# brobot19.net
KiCad netlist of a schematic drawn in EAGLE
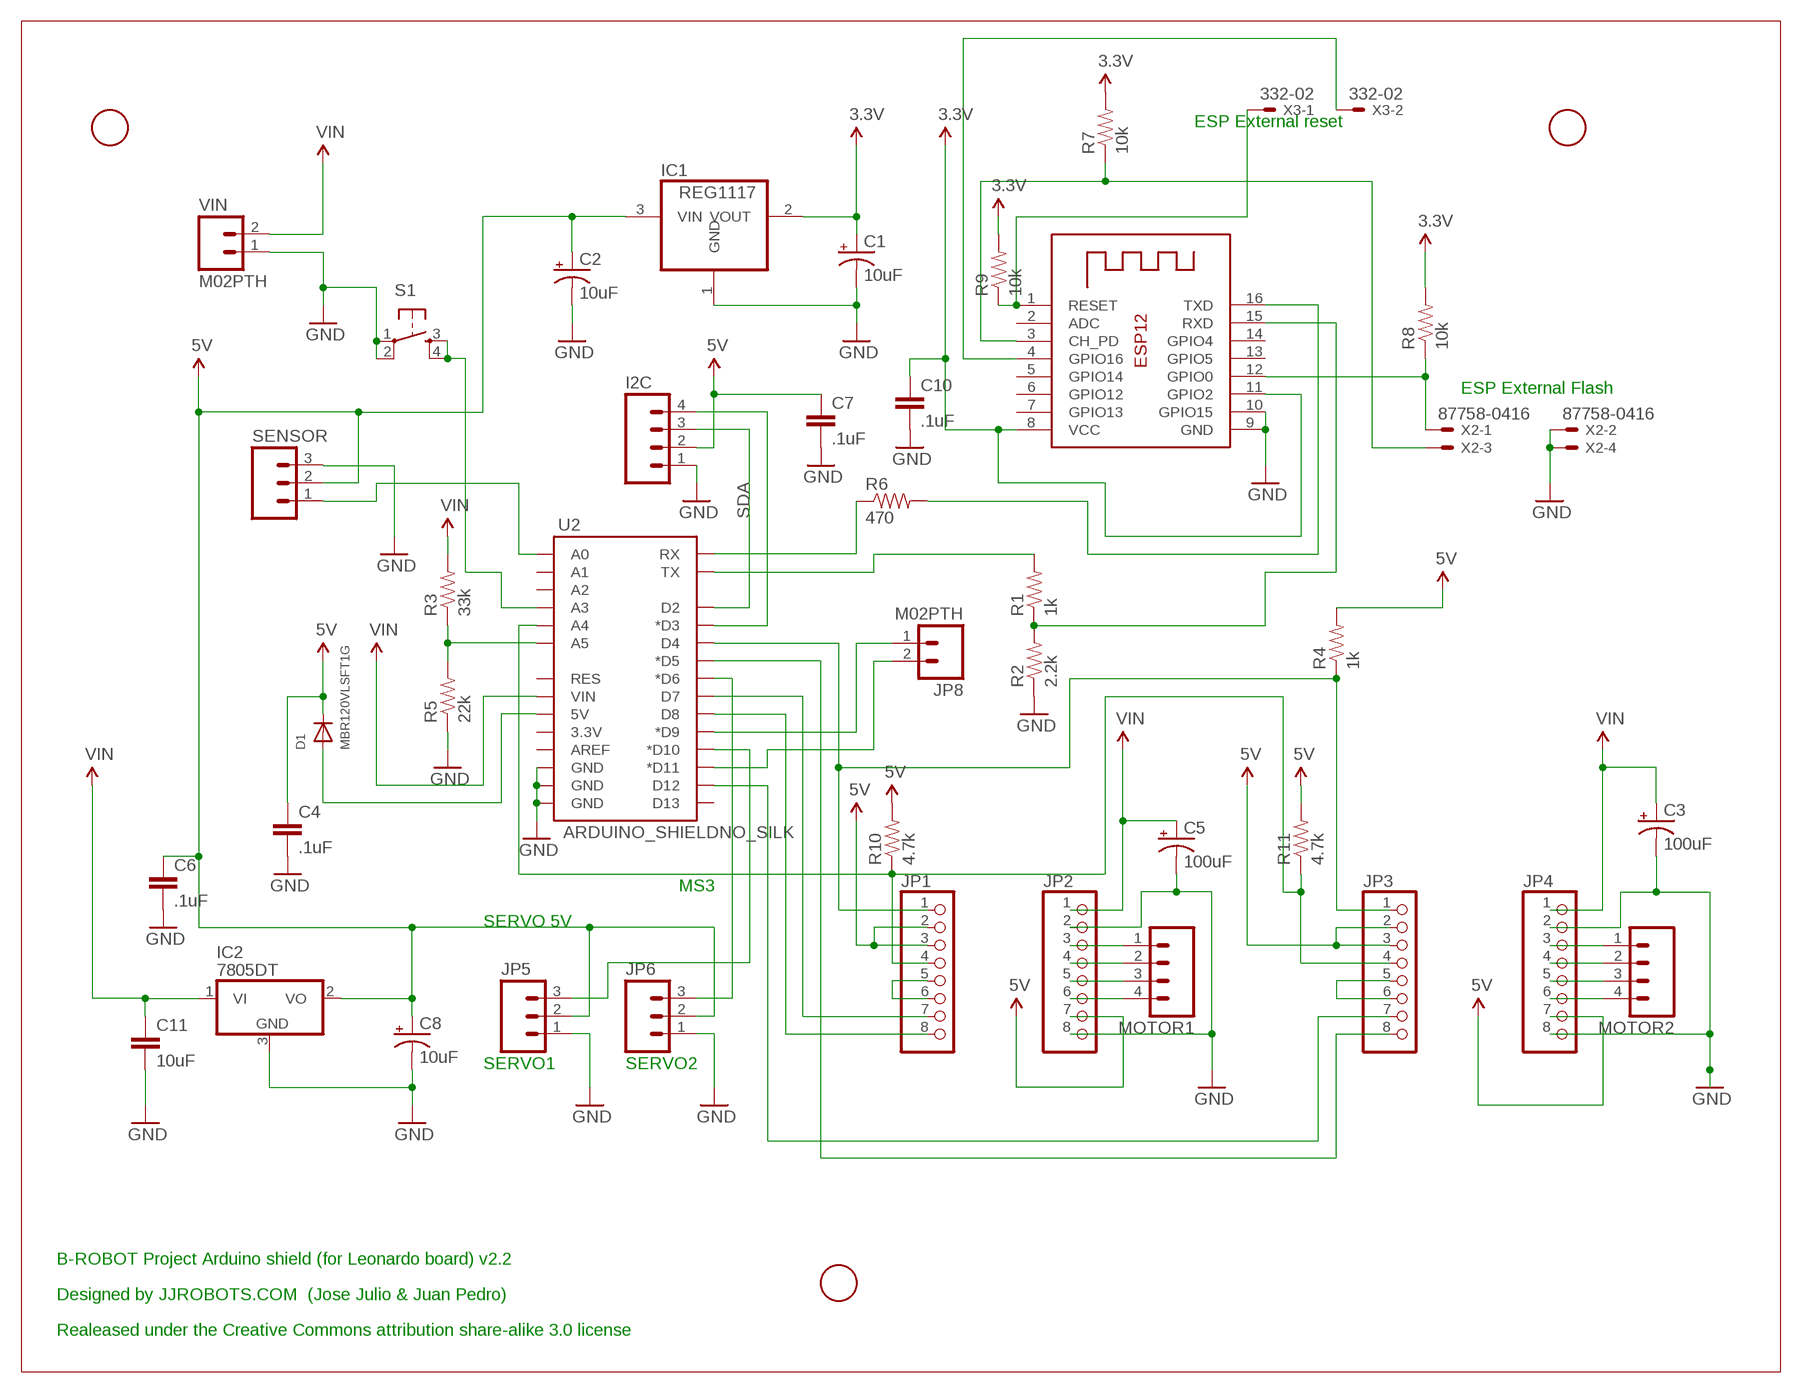
[diagram p0: schematic, sheet 1]

(export (version "E")
  (design (tool "Eeschema 10.0.6"))
  (components
    (comp (ref "C1")
      (value "10uF")
      (footprint "eagle-import:EIA3216")
      (libsource (lib "eagle-import") (part "CAP_POL1206"))
    )
    (comp (ref "C2")
      (value "10uF")
      (footprint "eagle-import:EIA3216")
      (libsource (lib "eagle-import") (part "CAP_POL1206"))
    )
    (comp (ref "C3")
      (value "100uF")
      (footprint "eagle-import:PANASONIC_D")
      (libsource (lib "eagle-import") (part "CAP_POLD"))
    )
    (comp (ref "C4")
      (value ".1uF")
      (footprint "eagle-import:0402-CAP")
      (libsource (lib "eagle-import") (part "CAP0402-CAP"))
    )
    (comp (ref "C5")
      (value "100uF")
      (footprint "eagle-import:PANASONIC_D")
      (libsource (lib "eagle-import") (part "CAP_POLD"))
    )
    (comp (ref "C6")
      (value ".1uF")
      (footprint "eagle-import:0402-CAP")
      (libsource (lib "eagle-import") (part "CAP0402-CAP"))
    )
    (comp (ref "C7")
      (value ".1uF")
      (footprint "eagle-import:0402-CAP")
      (libsource (lib "eagle-import") (part "CAP0402-CAP"))
    )
    (comp (ref "C8")
      (value "10uF")
      (footprint "eagle-import:EIA3216")
      (libsource (lib "eagle-import") (part "CAP_POL1206"))
    )
    (comp (ref "C10")
      (value ".1uF")
      (footprint "eagle-import:0402-CAP")
      (libsource (lib "eagle-import") (part "CAP0402-CAP"))
    )
    (comp (ref "C11")
      (value "10uF")
      (footprint "eagle-import:1206")
      (libsource (lib "eagle-import") (part "CAP1206"))
    )
    (comp (ref "D1")
      (value "MBR120VLSFT1G")
      (footprint "eagle-import:SOD-123")
      (libsource (lib "eagle-import") (part "DIODESOD-123"))
    )
    (comp (ref "I2C")
      (value "M04PTH")
      (footprint "eagle-import:1X04")
      (libsource (lib "eagle-import") (part "M04PTH"))
    )
    (comp (ref "IC1")
      (value "REG1117")
      (footprint "eagle-import:SOT223")
      (fields (field (name "MF") "LM1117MPX-3.3/NOPB"))
      (libsource (lib "eagle-import") (part "REG1117"))
    )
    (comp (ref "IC2")
      (value "7805DT")
      (footprint "eagle-import:TO252")
      (libsource (lib "eagle-import") (part "78DT05"))
    )
    (comp (ref "JP1")
      (value "PINHD-1X8")
      (footprint "eagle-import:1X08")
      (libsource (lib "eagle-import") (part "PINHD-1X8"))
    )
    (comp (ref "JP2")
      (value "PINHD-1X8")
      (footprint "eagle-import:1X08")
      (libsource (lib "eagle-import") (part "PINHD-1X8"))
    )
    (comp (ref "JP3")
      (value "PINHD-1X8")
      (footprint "eagle-import:1X08")
      (libsource (lib "eagle-import") (part "PINHD-1X8"))
    )
    (comp (ref "JP4")
      (value "PINHD-1X8")
      (footprint "eagle-import:1X08")
      (libsource (lib "eagle-import") (part "PINHD-1X8"))
    )
    (comp (ref "JP5")
      (value "M03PTH")
      (footprint "eagle-import:1X03")
      (libsource (lib "eagle-import") (part "M03PTH"))
    )
    (comp (ref "JP6")
      (value "M03PTH")
      (footprint "eagle-import:1X03")
      (libsource (lib "eagle-import") (part "M03PTH"))
    )
    (comp (ref "JP8")
      (value "M02PTH")
      (footprint "eagle-import:1X02")
      (libsource (lib "eagle-import") (part "M02PTH"))
    )
    (comp (ref "MOTOR1")
      (value "M04PTH")
      (footprint "eagle-import:1X04")
      (libsource (lib "eagle-import") (part "M04PTH"))
    )
    (comp (ref "MOTOR2")
      (value "M04PTH")
      (footprint "eagle-import:1X04")
      (libsource (lib "eagle-import") (part "M04PTH"))
    )
    (comp (ref "R1")
      (value "1k")
      (footprint "eagle-import:0805")
      (libsource (lib "eagle-import") (part "RESISTOR0805-RES"))
    )
    (comp (ref "R2")
      (value "2.2k")
      (footprint "eagle-import:0805")
      (libsource (lib "eagle-import") (part "RESISTOR0805-RES"))
    )
    (comp (ref "R3")
      (value "33k")
      (footprint "eagle-import:0805")
      (libsource (lib "eagle-import") (part "RESISTOR0805-RES"))
    )
    (comp (ref "R4")
      (value "1k")
      (footprint "eagle-import:0805")
      (libsource (lib "eagle-import") (part "RESISTOR0805-RES"))
    )
    (comp (ref "R5")
      (value "22k")
      (footprint "eagle-import:0805")
      (libsource (lib "eagle-import") (part "RESISTOR0805-RES"))
    )
    (comp (ref "R6")
      (value "470")
      (footprint "eagle-import:0805")
      (libsource (lib "eagle-import") (part "RESISTOR0805-RES"))
    )
    (comp (ref "R7")
      (value "10k")
      (footprint "eagle-import:0805")
      (libsource (lib "eagle-import") (part "RESISTOR0805-RES"))
    )
    (comp (ref "R8")
      (value "10k")
      (footprint "eagle-import:0805")
      (libsource (lib "eagle-import") (part "RESISTOR0805-RES"))
    )
    (comp (ref "R9")
      (value "10k")
      (footprint "eagle-import:0805")
      (libsource (lib "eagle-import") (part "RESISTOR0805-RES"))
    )
    (comp (ref "R10")
      (value "4.7k")
      (footprint "eagle-import:0805")
      (libsource (lib "eagle-import") (part "RESISTOR0805-RES"))
    )
    (comp (ref "R11")
      (value "4.7k")
      (footprint "eagle-import:0805")
      (libsource (lib "eagle-import") (part "RESISTOR0805-RES"))
    )
    (comp (ref "S1")
      (value "TAC_SWITCHSMD")
      (footprint "eagle-import:TACTILE-SWITCH-SMD")
      (libsource (lib "eagle-import") (part "TAC_SWITCHSMD"))
    )
    (comp (ref "SENSOR")
      (value "M03PTH")
      (footprint "eagle-import:1X03")
      (libsource (lib "eagle-import") (part "M03PTH"))
    )
    (comp (ref "U$1")
      (value "FIDUCIAL")
      (footprint "eagle-import:FIDUCIAL_1MM")
      (libsource (lib "eagle-import") (part "FIDUCIAL"))
    )
    (comp (ref "U$2")
      (value "FIDUCIAL")
      (footprint "eagle-import:FIDUCIAL_1MM")
      (libsource (lib "eagle-import") (part "FIDUCIAL"))
    )
    (comp (ref "U$3")
      (value "FIDUCIAL")
      (footprint "eagle-import:FIDUCIAL_1MM")
      (libsource (lib "eagle-import") (part "FIDUCIAL"))
    )
    (comp (ref "U2")
      (value "ARDUINO_SHIELDNO_SILK")
      (footprint "eagle-import:DUEMILANOVE_VIAS")
      (libsource (lib "eagle-import") (part "ARDUINO_SHIELDNO_SILK"))
    )
    (comp (ref "VIN")
      (value "M02PTH")
      (footprint "eagle-import:1X02")
      (libsource (lib "eagle-import") (part "M02PTH"))
    )
    (comp (ref "X1")
      (value "ESP-12")
      (footprint "eagle-import:ESP-12")
      (libsource (lib "eagle-import") (part "ESP-12"))
    )
    (comp (ref "X2")
      (value "87758-0416")
      (footprint "eagle-import:87758-0416")
      (fields (field (name "MF") "FARNELL"))
      (libsource (lib "eagle-import") (part "87758-0416"))
    )
    (comp (ref "X3")
      (value "332-02")
      (footprint "eagle-import:332-02")
      (libsource (lib "eagle-import") (part "332-02"))
    )
  )
  (nets
    (net (code "1") (name "/SDA") (class "Default")
      (node (ref "I2C") (pin "3") (pinfunction "3_3") (pintype "passive"))
      (node (ref "U2") (pin "D2") (pinfunction "D2_D2") (pintype "bidirectional"))
    )
    (net (code "2") (name "3.3V") (class "Default")
      (node (ref "C1") (pin "A") (pinfunction "+_A") (pintype "passive"))
      (node (ref "C10") (pin "1") (pinfunction "1_1") (pintype "passive"))
      (node (ref "IC1") (pin "2") (pinfunction "VOUT_2") (pintype "output"))
      (node (ref "R7") (pin "2") (pinfunction "2_2") (pintype "passive"))
      (node (ref "R8") (pin "2") (pinfunction "2_2") (pintype "passive"))
      (node (ref "R9") (pin "2") (pinfunction "2_2") (pintype "passive"))
      (node (ref "X1") (pin "11") (pinfunction "GPIO2_11") (pintype "bidirectional"))
      (node (ref "X1") (pin "8") (pinfunction "VCC_8") (pintype "power_in"))
    )
    (net (code "3") (name "5V") (class "Default")
      (node (ref "C2") (pin "A") (pinfunction "+_A") (pintype "passive"))
      (node (ref "C4") (pin "1") (pinfunction "1_1") (pintype "passive"))
      (node (ref "C6") (pin "1") (pinfunction "1_1") (pintype "passive"))
      (node (ref "C7") (pin "1") (pinfunction "1_1") (pintype "passive"))
      (node (ref "C8") (pin "A") (pinfunction "+_A") (pintype "passive"))
      (node (ref "D1") (pin "C") (pinfunction "C_C") (pintype "passive"))
      (node (ref "I2C") (pin "2") (pinfunction "2_2") (pintype "passive"))
      (node (ref "IC1") (pin "3") (pinfunction "VIN_3") (pintype "input"))
      (node (ref "IC2") (pin "2") (pinfunction "VO_2") (pintype "passive"))
      (node (ref "JP1") (pin "2") (pinfunction "2_2") (pintype "passive"))
      (node (ref "JP1") (pin "3") (pinfunction "3_3") (pintype "passive"))
      (node (ref "JP2") (pin "7") (pinfunction "7_7") (pintype "passive"))
      (node (ref "JP3") (pin "2") (pinfunction "2_2") (pintype "passive"))
      (node (ref "JP3") (pin "3") (pinfunction "3_3") (pintype "passive"))
      (node (ref "JP4") (pin "7") (pinfunction "7_7") (pintype "passive"))
      (node (ref "JP5") (pin "2") (pinfunction "2_2") (pintype "passive"))
      (node (ref "JP6") (pin "2") (pinfunction "2_2") (pintype "passive"))
      (node (ref "R10") (pin "2") (pinfunction "2_2") (pintype "passive"))
      (node (ref "R11") (pin "2") (pinfunction "2_2") (pintype "passive"))
      (node (ref "R4") (pin "2") (pinfunction "2_2") (pintype "passive"))
      (node (ref "SENSOR") (pin "2") (pinfunction "2_2") (pintype "passive"))
    )
    (net (code "4") (name "GND") (class "Default")
      (node (ref "C1") (pin "C") (pinfunction "-_C") (pintype "passive"))
      (node (ref "C10") (pin "2") (pinfunction "2_2") (pintype "passive"))
      (node (ref "C11") (pin "2") (pinfunction "2_2") (pintype "passive"))
      (node (ref "C2") (pin "C") (pinfunction "-_C") (pintype "passive"))
      (node (ref "C3") (pin "-") (pinfunction "-_-") (pintype "passive"))
      (node (ref "C4") (pin "2") (pinfunction "2_2") (pintype "passive"))
      (node (ref "C5") (pin "-") (pinfunction "-_-") (pintype "passive"))
      (node (ref "C6") (pin "2") (pinfunction "2_2") (pintype "passive"))
      (node (ref "C7") (pin "2") (pinfunction "2_2") (pintype "passive"))
      (node (ref "C8") (pin "C") (pinfunction "-_C") (pintype "passive"))
      (node (ref "I2C") (pin "1") (pinfunction "1_1") (pintype "passive"))
      (node (ref "IC1") (pin "1") (pinfunction "GND_1") (pintype "power_in"))
      (node (ref "IC2") (pin "3") (pinfunction "GND_3") (pintype "passive"))
      (node (ref "JP2") (pin "2") (pinfunction "2_2") (pintype "passive"))
      (node (ref "JP2") (pin "8") (pinfunction "8_8") (pintype "passive"))
      (node (ref "JP4") (pin "2") (pinfunction "2_2") (pintype "passive"))
      (node (ref "JP4") (pin "8") (pinfunction "8_8") (pintype "passive"))
      (node (ref "JP5") (pin "1") (pinfunction "1_1") (pintype "passive"))
      (node (ref "JP6") (pin "1") (pinfunction "1_1") (pintype "passive"))
      (node (ref "R2") (pin "1") (pinfunction "1_1") (pintype "passive"))
      (node (ref "R5") (pin "1") (pinfunction "1_1") (pintype "passive"))
      (node (ref "S1") (pin "1") (pinfunction "1_1") (pintype "passive"))
      (node (ref "S1") (pin "2") (pinfunction "2_2") (pintype "passive"))
      (node (ref "SENSOR") (pin "3") (pinfunction "3_3") (pintype "passive"))
      (node (ref "U2") (pin "GND@0") (pinfunction "GND_GND@0") (pintype "bidirectional"))
      (node (ref "U2") (pin "GND@1") (pinfunction "GND_GND@1") (pintype "bidirectional"))
      (node (ref "U2") (pin "GND@2") (pinfunction "GND_GND@2") (pintype "bidirectional"))
      (node (ref "VIN") (pin "1") (pinfunction "1_1") (pintype "passive"))
      (node (ref "X1") (pin "10") (pinfunction "GPIO15_10") (pintype "bidirectional"))
      (node (ref "X1") (pin "9") (pinfunction "GND_9") (pintype "power_in"))
      (node (ref "X2") (pin "2") (pinfunction "S_2") (pintype "passive"))
      (node (ref "X2") (pin "4") (pinfunction "S_4") (pintype "passive"))
    )
    (net (code "5") (name "Net-(D1-PadA)") (class "Default")
      (node (ref "D1") (pin "A") (pinfunction "A_A") (pintype "passive"))
      (node (ref "U2") (pin "5V") (pinfunction "5V_5V") (pintype "bidirectional"))
    )
    (net (code "6") (name "Net-(JP1-Pad1)") (class "Default")
      (node (ref "JP1") (pin "1") (pinfunction "1_1") (pintype "passive"))
      (node (ref "JP3") (pin "1") (pinfunction "1_1") (pintype "passive"))
      (node (ref "R4") (pin "1") (pinfunction "1_1") (pintype "passive"))
      (node (ref "U2") (pin "D4") (pinfunction "D4_D4") (pintype "bidirectional"))
    )
    (net (code "7") (name "Net-(JP1-Pad4)") (class "Default")
      (node (ref "JP1") (pin "4") (pinfunction "4_4") (pintype "passive"))
      (node (ref "JP3") (pin "4") (pinfunction "4_4") (pintype "passive"))
      (node (ref "R10") (pin "1") (pinfunction "1_1") (pintype "passive"))
      (node (ref "R11") (pin "1") (pinfunction "1_1") (pintype "passive"))
      (node (ref "U2") (pin "A4") (pinfunction "A4_A4") (pintype "bidirectional"))
    )
    (net (code "8") (name "Net-(JP1-Pad5)") (class "Default")
      (node (ref "JP1") (pin "5") (pinfunction "5_5") (pintype "passive"))
      (node (ref "JP1") (pin "6") (pinfunction "6_6") (pintype "passive"))
    )
    (net (code "9") (name "Net-(JP1-Pad7)") (class "Default")
      (node (ref "JP1") (pin "7") (pinfunction "7_7") (pintype "passive"))
      (node (ref "U2") (pin "D7") (pinfunction "D7_D7") (pintype "bidirectional"))
    )
    (net (code "10") (name "Net-(JP1-Pad8)") (class "Default")
      (node (ref "JP1") (pin "8") (pinfunction "8_8") (pintype "passive"))
      (node (ref "U2") (pin "D8") (pinfunction "D8_D8") (pintype "bidirectional"))
    )
    (net (code "11") (name "Net-(JP2-Pad3)") (class "Default")
      (node (ref "JP2") (pin "3") (pinfunction "3_3") (pintype "passive"))
      (node (ref "MOTOR1") (pin "1") (pinfunction "1_1") (pintype "passive"))
    )
    (net (code "12") (name "Net-(JP2-Pad4)") (class "Default")
      (node (ref "JP2") (pin "4") (pinfunction "4_4") (pintype "passive"))
      (node (ref "MOTOR1") (pin "2") (pinfunction "2_2") (pintype "passive"))
    )
    (net (code "13") (name "Net-(JP2-Pad5)") (class "Default")
      (node (ref "JP2") (pin "5") (pinfunction "5_5") (pintype "passive"))
      (node (ref "MOTOR1") (pin "3") (pinfunction "3_3") (pintype "passive"))
    )
    (net (code "14") (name "Net-(JP2-Pad6)") (class "Default")
      (node (ref "JP2") (pin "6") (pinfunction "6_6") (pintype "passive"))
      (node (ref "MOTOR1") (pin "4") (pinfunction "4_4") (pintype "passive"))
    )
    (net (code "15") (name "Net-(JP3-Pad5)") (class "Default")
      (node (ref "JP3") (pin "5") (pinfunction "5_5") (pintype "passive"))
      (node (ref "JP3") (pin "6") (pinfunction "6_6") (pintype "passive"))
    )
    (net (code "16") (name "Net-(JP3-Pad7)") (class "Default")
      (node (ref "JP3") (pin "7") (pinfunction "7_7") (pintype "passive"))
      (node (ref "U2") (pin "D12") (pinfunction "D12_D12") (pintype "bidirectional"))
    )
    (net (code "17") (name "Net-(JP4-Pad3)") (class "Default")
      (node (ref "JP4") (pin "3") (pinfunction "3_3") (pintype "passive"))
      (node (ref "MOTOR2") (pin "1") (pinfunction "1_1") (pintype "passive"))
    )
    (net (code "18") (name "Net-(JP4-Pad4)") (class "Default")
      (node (ref "JP4") (pin "4") (pinfunction "4_4") (pintype "passive"))
      (node (ref "MOTOR2") (pin "2") (pinfunction "2_2") (pintype "passive"))
    )
    (net (code "19") (name "Net-(JP4-Pad5)") (class "Default")
      (node (ref "JP4") (pin "5") (pinfunction "5_5") (pintype "passive"))
      (node (ref "MOTOR2") (pin "3") (pinfunction "3_3") (pintype "passive"))
    )
    (net (code "20") (name "Net-(JP4-Pad6)") (class "Default")
      (node (ref "JP4") (pin "6") (pinfunction "6_6") (pintype "passive"))
      (node (ref "MOTOR2") (pin "4") (pinfunction "4_4") (pintype "passive"))
    )
    (net (code "21") (name "Net-(R1-Pad2)") (class "Default")
      (node (ref "R1") (pin "2") (pinfunction "2_2") (pintype "passive"))
      (node (ref "U2") (pin "TX") (pinfunction "TX_TX") (pintype "bidirectional"))
    )
    (net (code "22") (name "Net-(R3-Pad1)") (class "Default")
      (node (ref "R3") (pin "1") (pinfunction "1_1") (pintype "passive"))
      (node (ref "R5") (pin "2") (pinfunction "2_2") (pintype "passive"))
      (node (ref "U2") (pin "A5") (pinfunction "A5_A5") (pintype "bidirectional"))
    )
    (net (code "23") (name "Net-(R6-Pad1)") (class "Default")
      (node (ref "R6") (pin "1") (pinfunction "1_1") (pintype "passive"))
      (node (ref "U2") (pin "RX") (pinfunction "RX_RX") (pintype "bidirectional"))
    )
    (net (code "24") (name "Net-(S1-Pad3)") (class "Default")
      (node (ref "S1") (pin "3") (pinfunction "3_3") (pintype "passive"))
      (node (ref "S1") (pin "4") (pinfunction "4_4") (pintype "passive"))
      (node (ref "U2") (pin "A3") (pinfunction "A3_A3") (pintype "bidirectional"))
    )
    (net (code "25") (name "Net-(SENSOR-Pad1)") (class "Default")
      (node (ref "SENSOR") (pin "1") (pinfunction "1_1") (pintype "passive"))
      (node (ref "U2") (pin "A0") (pinfunction "A0_A0") (pintype "bidirectional"))
    )
    (net (code "26") (name "Net-(U2-*D3)") (class "Default")
      (node (ref "I2C") (pin "4") (pinfunction "4_4") (pintype "passive"))
      (node (ref "U2") (pin "D3") (pinfunction "*D3_D3") (pintype "bidirectional"))
    )
    (net (code "27") (name "Net-(U2-*D5)") (class "Default")
      (node (ref "JP3") (pin "8") (pinfunction "8_8") (pintype "passive"))
      (node (ref "U2") (pin "D5") (pinfunction "*D5_D5") (pintype "bidirectional"))
    )
    (net (code "28") (name "Net-(U2-*D6)") (class "Default")
      (node (ref "JP6") (pin "3") (pinfunction "3_3") (pintype "passive"))
      (node (ref "U2") (pin "D6") (pinfunction "*D6_D6") (pintype "bidirectional"))
    )
    (net (code "29") (name "Net-(U2-*D9)") (class "Default")
      (node (ref "JP8") (pin "1") (pinfunction "1_1") (pintype "passive"))
      (node (ref "U2") (pin "D9") (pinfunction "*D9_D9") (pintype "bidirectional"))
    )
    (net (code "30") (name "Net-(U2-*D10)") (class "Default")
      (node (ref "JP5") (pin "3") (pinfunction "3_3") (pintype "passive"))
      (node (ref "U2") (pin "D10") (pinfunction "*D10_D10") (pintype "bidirectional"))
    )
    (net (code "31") (name "Net-(U2-*D11)") (class "Default")
      (node (ref "JP8") (pin "2") (pinfunction "2_2") (pintype "passive"))
      (node (ref "U2") (pin "D11") (pinfunction "*D11_D11") (pintype "bidirectional"))
    )
    (net (code "32") (name "Net-(X1-CH_PD)") (class "Default")
      (node (ref "R7") (pin "1") (pinfunction "1_1") (pintype "passive"))
      (node (ref "X1") (pin "3") (pinfunction "CH_PD_3") (pintype "input"))
      (node (ref "X2") (pin "3") (pinfunction "S_3") (pintype "passive"))
    )
    (net (code "33") (name "Net-(X1-GPIO0)") (class "Default")
      (node (ref "R8") (pin "1") (pinfunction "1_1") (pintype "passive"))
      (node (ref "X1") (pin "12") (pinfunction "GPIO0_12") (pintype "bidirectional"))
      (node (ref "X2") (pin "1") (pinfunction "S_1") (pintype "passive"))
    )
    (net (code "34") (name "Net-(X1-GPIO16)") (class "Default")
      (node (ref "X1") (pin "4") (pinfunction "GPIO16_4") (pintype "bidirectional"))
      (node (ref "X3") (pin "2") (pinfunction "S_2") (pintype "passive"))
    )
    (net (code "35") (name "Net-(X1-RESET)") (class "Default")
      (node (ref "R9") (pin "1") (pinfunction "1_1") (pintype "passive"))
      (node (ref "X1") (pin "1") (pinfunction "RESET_1") (pintype "input"))
      (node (ref "X3") (pin "1") (pinfunction "S_1") (pintype "passive"))
    )
    (net (code "36") (name "Net-(X1-RXD)") (class "Default")
      (node (ref "R1") (pin "1") (pinfunction "1_1") (pintype "passive"))
      (node (ref "R2") (pin "2") (pinfunction "2_2") (pintype "passive"))
      (node (ref "X1") (pin "15") (pinfunction "RXD_15") (pintype "input"))
    )
    (net (code "37") (name "Net-(X1-TXD)") (class "Default")
      (node (ref "R6") (pin "2") (pinfunction "2_2") (pintype "passive"))
      (node (ref "X1") (pin "16") (pinfunction "TXD_16") (pintype "output"))
    )
    (net (code "38") (name "VIN") (class "Default")
      (node (ref "C11") (pin "1") (pinfunction "1_1") (pintype "passive"))
      (node (ref "C3") (pin "+") (pinfunction "+_+") (pintype "passive"))
      (node (ref "C5") (pin "+") (pinfunction "+_+") (pintype "passive"))
      (node (ref "IC2") (pin "1") (pinfunction "VI_1") (pintype "input"))
      (node (ref "JP2") (pin "1") (pinfunction "1_1") (pintype "passive"))
      (node (ref "JP4") (pin "1") (pinfunction "1_1") (pintype "passive"))
      (node (ref "R3") (pin "2") (pinfunction "2_2") (pintype "passive"))
      (node (ref "U2") (pin "VIN") (pinfunction "VIN_VIN") (pintype "bidirectional"))
      (node (ref "VIN") (pin "2") (pinfunction "2_2") (pintype "passive"))
    )
    (net (code "39") (name "unconnected-(U2-Pad3.3V)") (class "Default")
      (node (ref "U2") (pin "3.3V") (pinfunction "3.3V_3.3V") (pintype "bidirectional"))
    )
    (net (code "40") (name "unconnected-(U2-PadA1)") (class "Default")
      (node (ref "U2") (pin "A1") (pinfunction "A1_A1") (pintype "bidirectional"))
    )
    (net (code "41") (name "unconnected-(U2-PadA2)") (class "Default")
      (node (ref "U2") (pin "A2") (pinfunction "A2_A2") (pintype "bidirectional"))
    )
    (net (code "42") (name "unconnected-(U2-PadAREF)") (class "Default")
      (node (ref "U2") (pin "AREF") (pinfunction "AREF_AREF") (pintype "bidirectional"))
    )
    (net (code "43") (name "unconnected-(U2-PadD13)") (class "Default")
      (node (ref "U2") (pin "D13") (pinfunction "D13_D13") (pintype "bidirectional"))
    )
    (net (code "44") (name "unconnected-(U2-PadRES)") (class "Default")
      (node (ref "U2") (pin "RES") (pinfunction "RES_RES") (pintype "bidirectional"))
    )
    (net (code "45") (name "unconnected-(X1-ADC-Pad2)") (class "Default")
      (node (ref "X1") (pin "2") (pinfunction "ADC_2") (pintype "passive"))
    )
    (net (code "46") (name "unconnected-(X1-GPIO4-Pad14)") (class "Default")
      (node (ref "X1") (pin "14") (pinfunction "GPIO4_14") (pintype "bidirectional"))
    )
    (net (code "47") (name "unconnected-(X1-GPIO5-Pad13)") (class "Default")
      (node (ref "X1") (pin "13") (pinfunction "GPIO5_13") (pintype "bidirectional"))
    )
    (net (code "48") (name "unconnected-(X1-GPIO12-Pad6)") (class "Default")
      (node (ref "X1") (pin "6") (pinfunction "GPIO12_6") (pintype "bidirectional"))
    )
    (net (code "49") (name "unconnected-(X1-GPIO13-Pad7)") (class "Default")
      (node (ref "X1") (pin "7") (pinfunction "GPIO13_7") (pintype "bidirectional"))
    )
    (net (code "50") (name "unconnected-(X1-GPIO14-Pad5)") (class "Default")
      (node (ref "X1") (pin "5") (pinfunction "GPIO14_5") (pintype "bidirectional"))
    )
  )
)
